# PlausibilityTrigger.net
KiCad netlist of a schematic drawn in Altium Designer
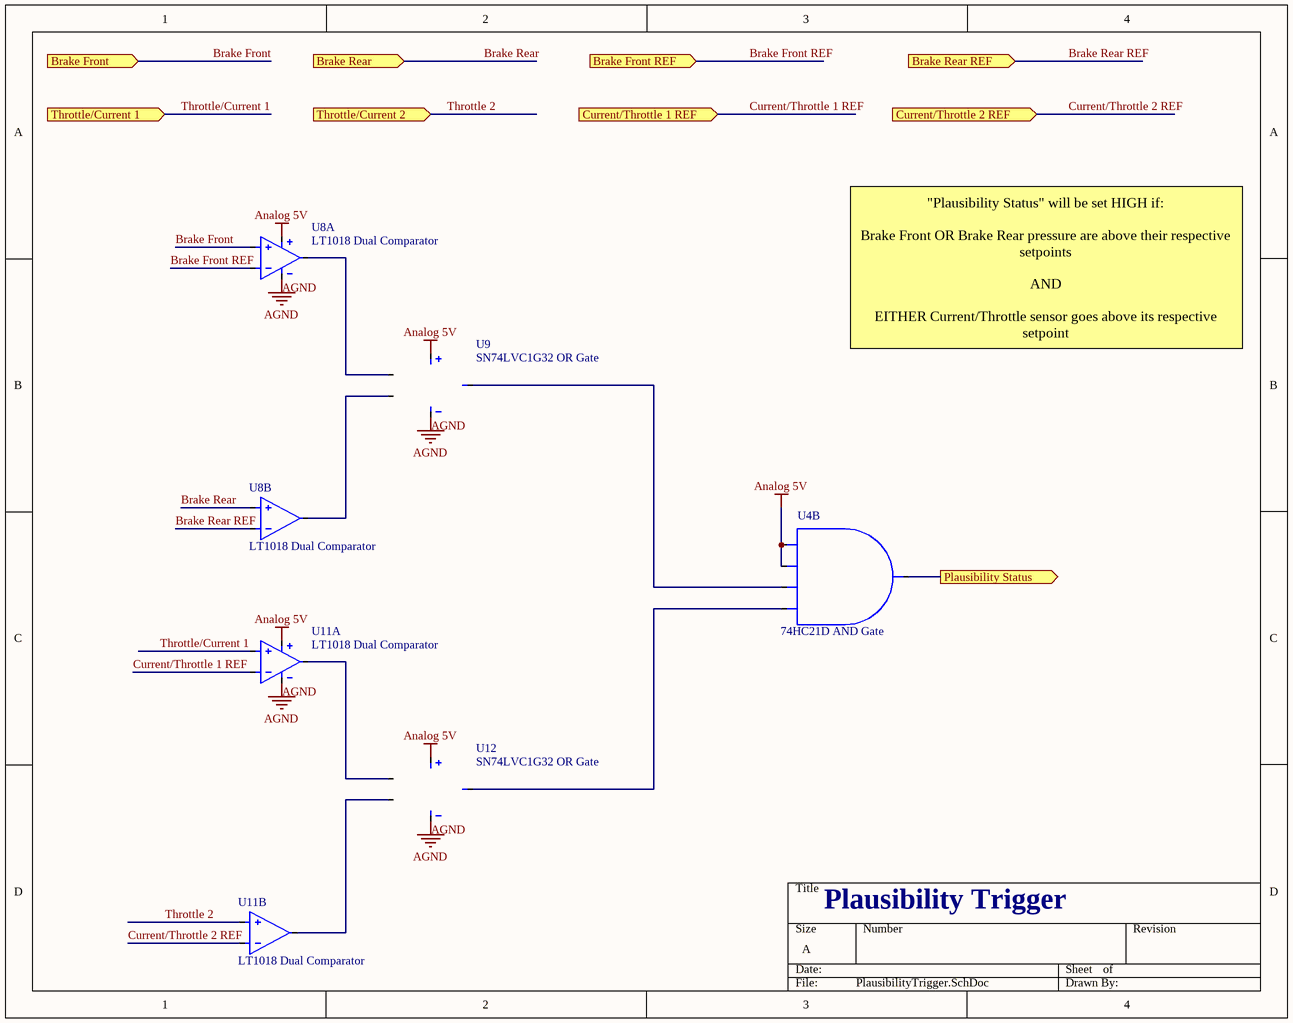
[diagram p0: PlausibilityTrigger.SchDoc]

(export (version "E")
  (design (tool "Eeschema 10.0.6"))
  (components
    (comp (ref "U4")
      (value "74HC21D AND Gate")
      (footprint "SOT108-1")
      (description "74HC21D_AND_Gate")
      (libsource (lib "altlib") (part "74HC21D AND Gate"))
    )
    (comp (ref "U8")
      (value "LT1018 Dual Comparator")
      (footprint "SOIC-8")
      (libsource (lib "altlib") (part "LT1018 Dual Comparator"))
    )
    (comp (ref "U9")
      (value "SN74LVC1G32 OR Gate")
      (footprint "SOT23-5")
      (description "SN74LVC1G32 OR GATE")
      (libsource (lib "altlib") (part "SN74LVC1G32 OR Gate"))
    )
    (comp (ref "U11")
      (value "LT1018 Dual Comparator")
      (footprint "SOIC-8")
      (libsource (lib "altlib") (part "LT1018 Dual Comparator"))
    )
    (comp (ref "U12")
      (value "SN74LVC1G32 OR Gate")
      (footprint "SOT23-5")
      (description "SN74LVC1G32 OR GATE")
      (libsource (lib "altlib") (part "SN74LVC1G32 OR Gate"))
    )
  )
  (nets
    (net (code "1") (name "/Brake Front") (class "Default")
      (node (ref "U8") (pin "1") (pinfunction "+IN_A_1") (pintype "passive"))
    )
    (net (code "2") (name "/Brake Front REF") (class "Default")
      (node (ref "U8") (pin "8") (pinfunction "-IN_A_8") (pintype "passive"))
    )
    (net (code "3") (name "/Brake Rear") (class "Default")
      (node (ref "U8") (pin "3") (pinfunction "+IN_B_3") (pintype "passive"))
    )
    (net (code "4") (name "/Brake Rear REF") (class "Default")
      (node (ref "U8") (pin "4") (pinfunction "-IN_B_4") (pintype "passive"))
    )
    (net (code "5") (name "/Current{slash}Throttle 1 REF") (class "Default")
      (node (ref "U11") (pin "8") (pinfunction "-IN_A_8") (pintype "passive"))
    )
    (net (code "6") (name "/Current{slash}Throttle 2 REF") (class "Default")
      (node (ref "U11") (pin "4") (pinfunction "-IN_B_4") (pintype "passive"))
    )
    (net (code "7") (name "/Plausibility Status") (class "Default")
      (node (ref "U4") (pin "8") (pinfunction "2Y_8") (pintype "passive"))
    )
    (net (code "8") (name "/Throttle 2") (class "Default")
      (node (ref "U11") (pin "3") (pinfunction "+IN_B_3") (pintype "passive"))
    )
    (net (code "9") (name "/Throttle{slash}Current 1") (class "Default")
      (node (ref "U11") (pin "1") (pinfunction "+IN_A_1") (pintype "passive"))
    )
    (net (code "10") (name "AGND") (class "Default")
      (node (ref "U11") (pin "2") (pinfunction "V-_2") (pintype "passive"))
      (node (ref "U12") (pin "3") (pinfunction "GND_3") (pintype "passive"))
      (node (ref "U8") (pin "2") (pinfunction "V-_2") (pintype "passive"))
      (node (ref "U9") (pin "3") (pinfunction "GND_3") (pintype "passive"))
    )
    (net (code "11") (name "Analog 5V") (class "Default")
      (node (ref "U11") (pin "6") (pinfunction "V+_6") (pintype "passive"))
      (node (ref "U12") (pin "5") (pinfunction "Vcc_5") (pintype "passive"))
      (node (ref "U4") (pin "10") (pinfunction "2B_10") (pintype "passive"))
      (node (ref "U4") (pin "9") (pinfunction "2A_9") (pintype "passive"))
      (node (ref "U8") (pin "6") (pinfunction "V+_6") (pintype "passive"))
      (node (ref "U9") (pin "5") (pinfunction "Vcc_5") (pintype "passive"))
    )
    (net (code "12") (name "Net-(U4B-2C)") (class "Default")
      (node (ref "U4") (pin "12") (pinfunction "2C_12") (pintype "passive"))
      (node (ref "U9") (pin "4") (pinfunction "B_4") (pintype "passive"))
    )
    (net (code "13") (name "Net-(U4B-2D)") (class "Default")
      (node (ref "U12") (pin "4") (pinfunction "B_4") (pintype "passive"))
      (node (ref "U4") (pin "13") (pinfunction "2D_13") (pintype "passive"))
    )
    (net (code "14") (name "Net-(U8A-OUT_A)") (class "Default")
      (node (ref "U8") (pin "7") (pinfunction "OUT_A_7") (pintype "passive"))
      (node (ref "U9") (pin "1") (pinfunction "A_1") (pintype "passive"))
    )
    (net (code "15") (name "Net-(U8B-OUT_B)") (class "Default")
      (node (ref "U8") (pin "5") (pinfunction "OUT_B_5") (pintype "passive"))
      (node (ref "U9") (pin "2") (pinfunction "B_2") (pintype "passive"))
    )
    (net (code "16") (name "Net-(U11A-OUT_A)") (class "Default")
      (node (ref "U11") (pin "7") (pinfunction "OUT_A_7") (pintype "passive"))
      (node (ref "U12") (pin "1") (pinfunction "A_1") (pintype "passive"))
    )
    (net (code "17") (name "Net-(U11B-OUT_B)") (class "Default")
      (node (ref "U11") (pin "5") (pinfunction "OUT_B_5") (pintype "passive"))
      (node (ref "U12") (pin "2") (pinfunction "B_2") (pintype "passive"))
    )
  )
)
